# SmartThermo1.net
KiCad netlist of a schematic drawn in EAGLE
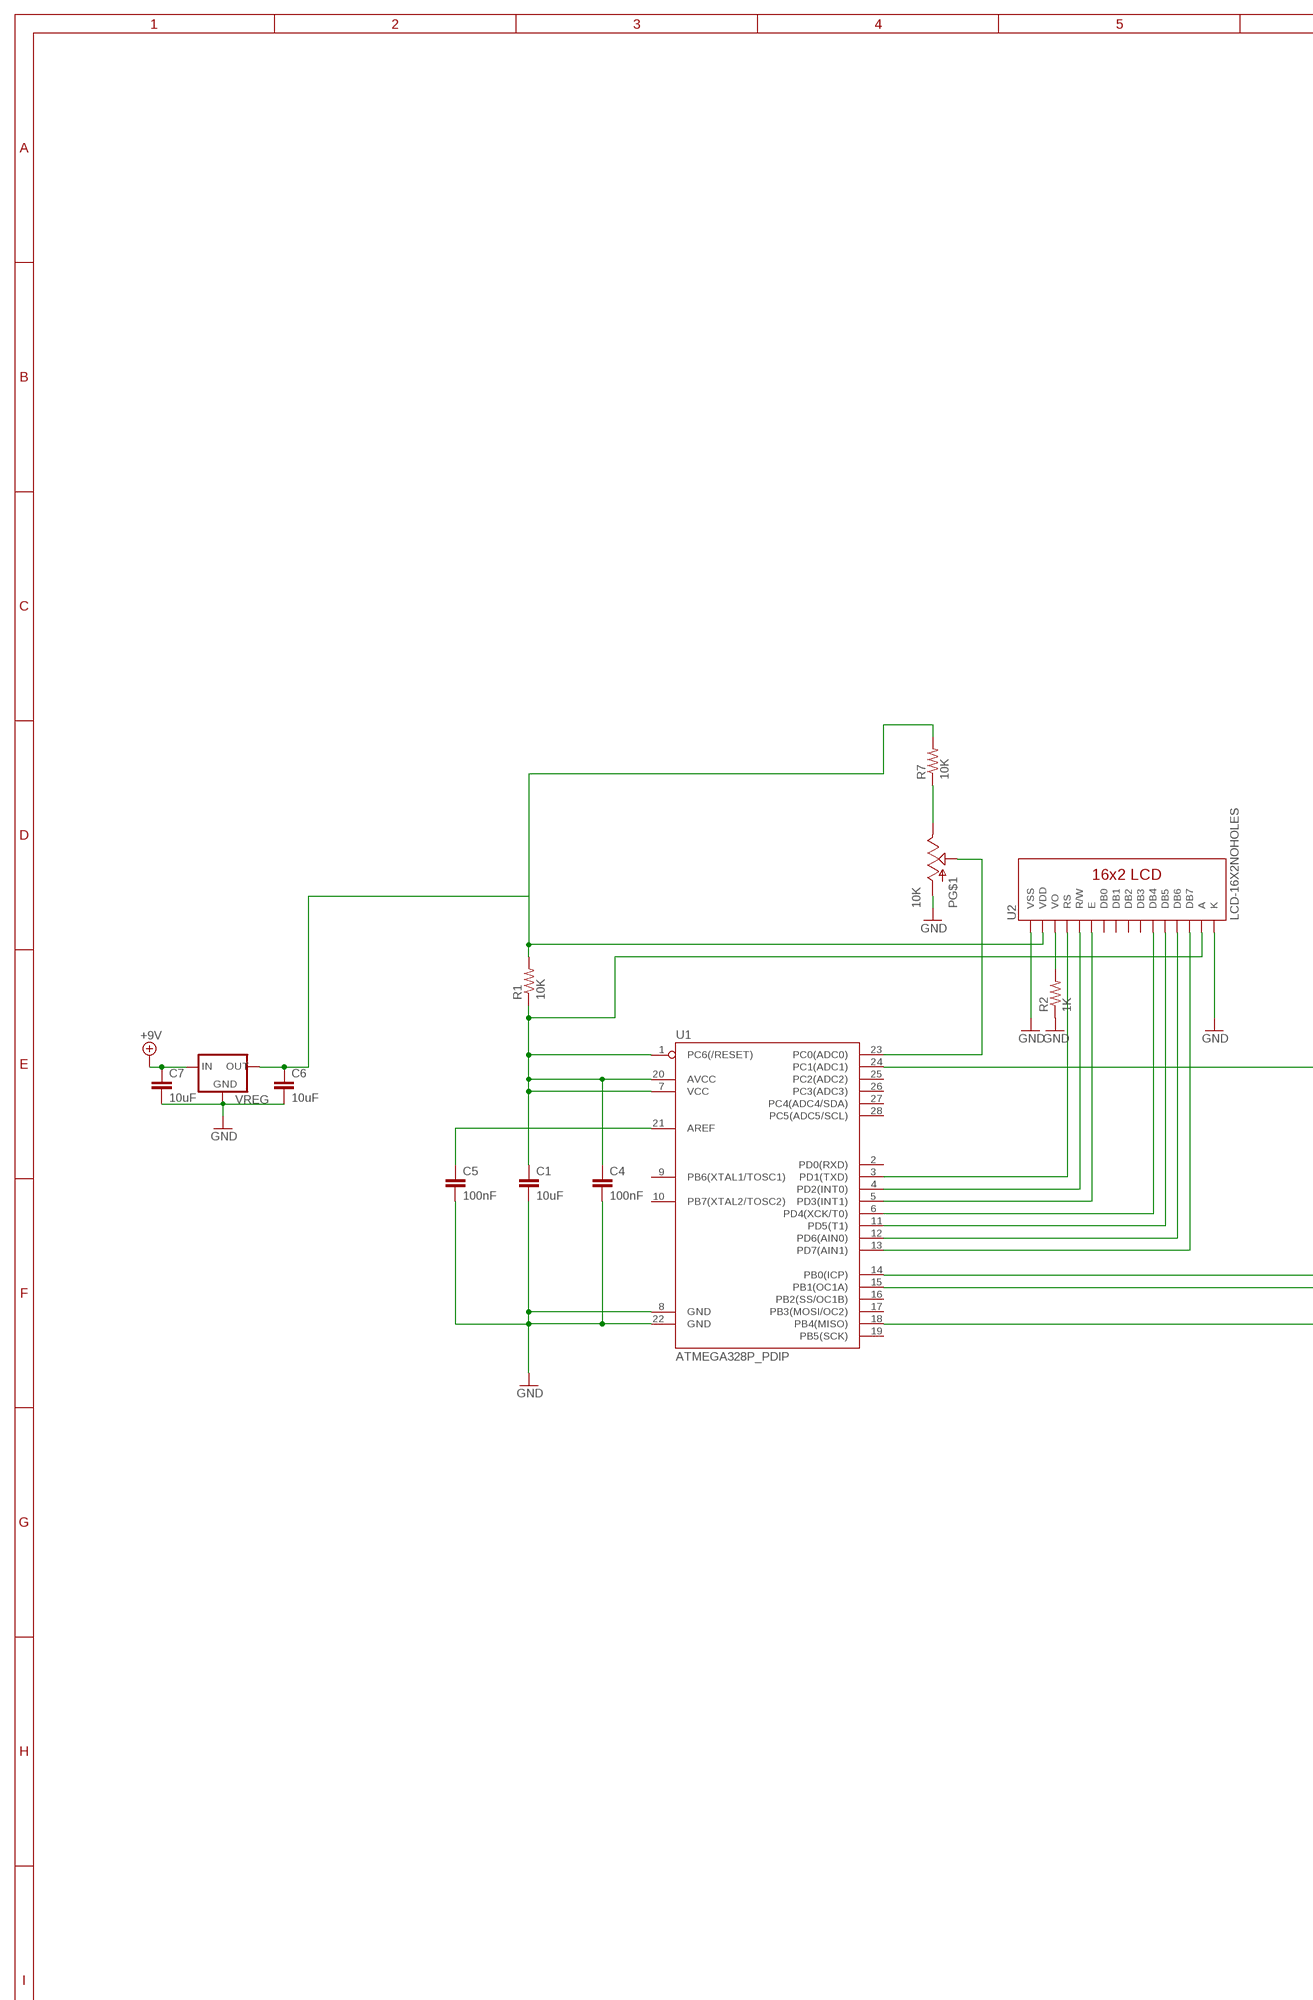
[diagram p0: schematic, sheet 1, part 1 of 2]
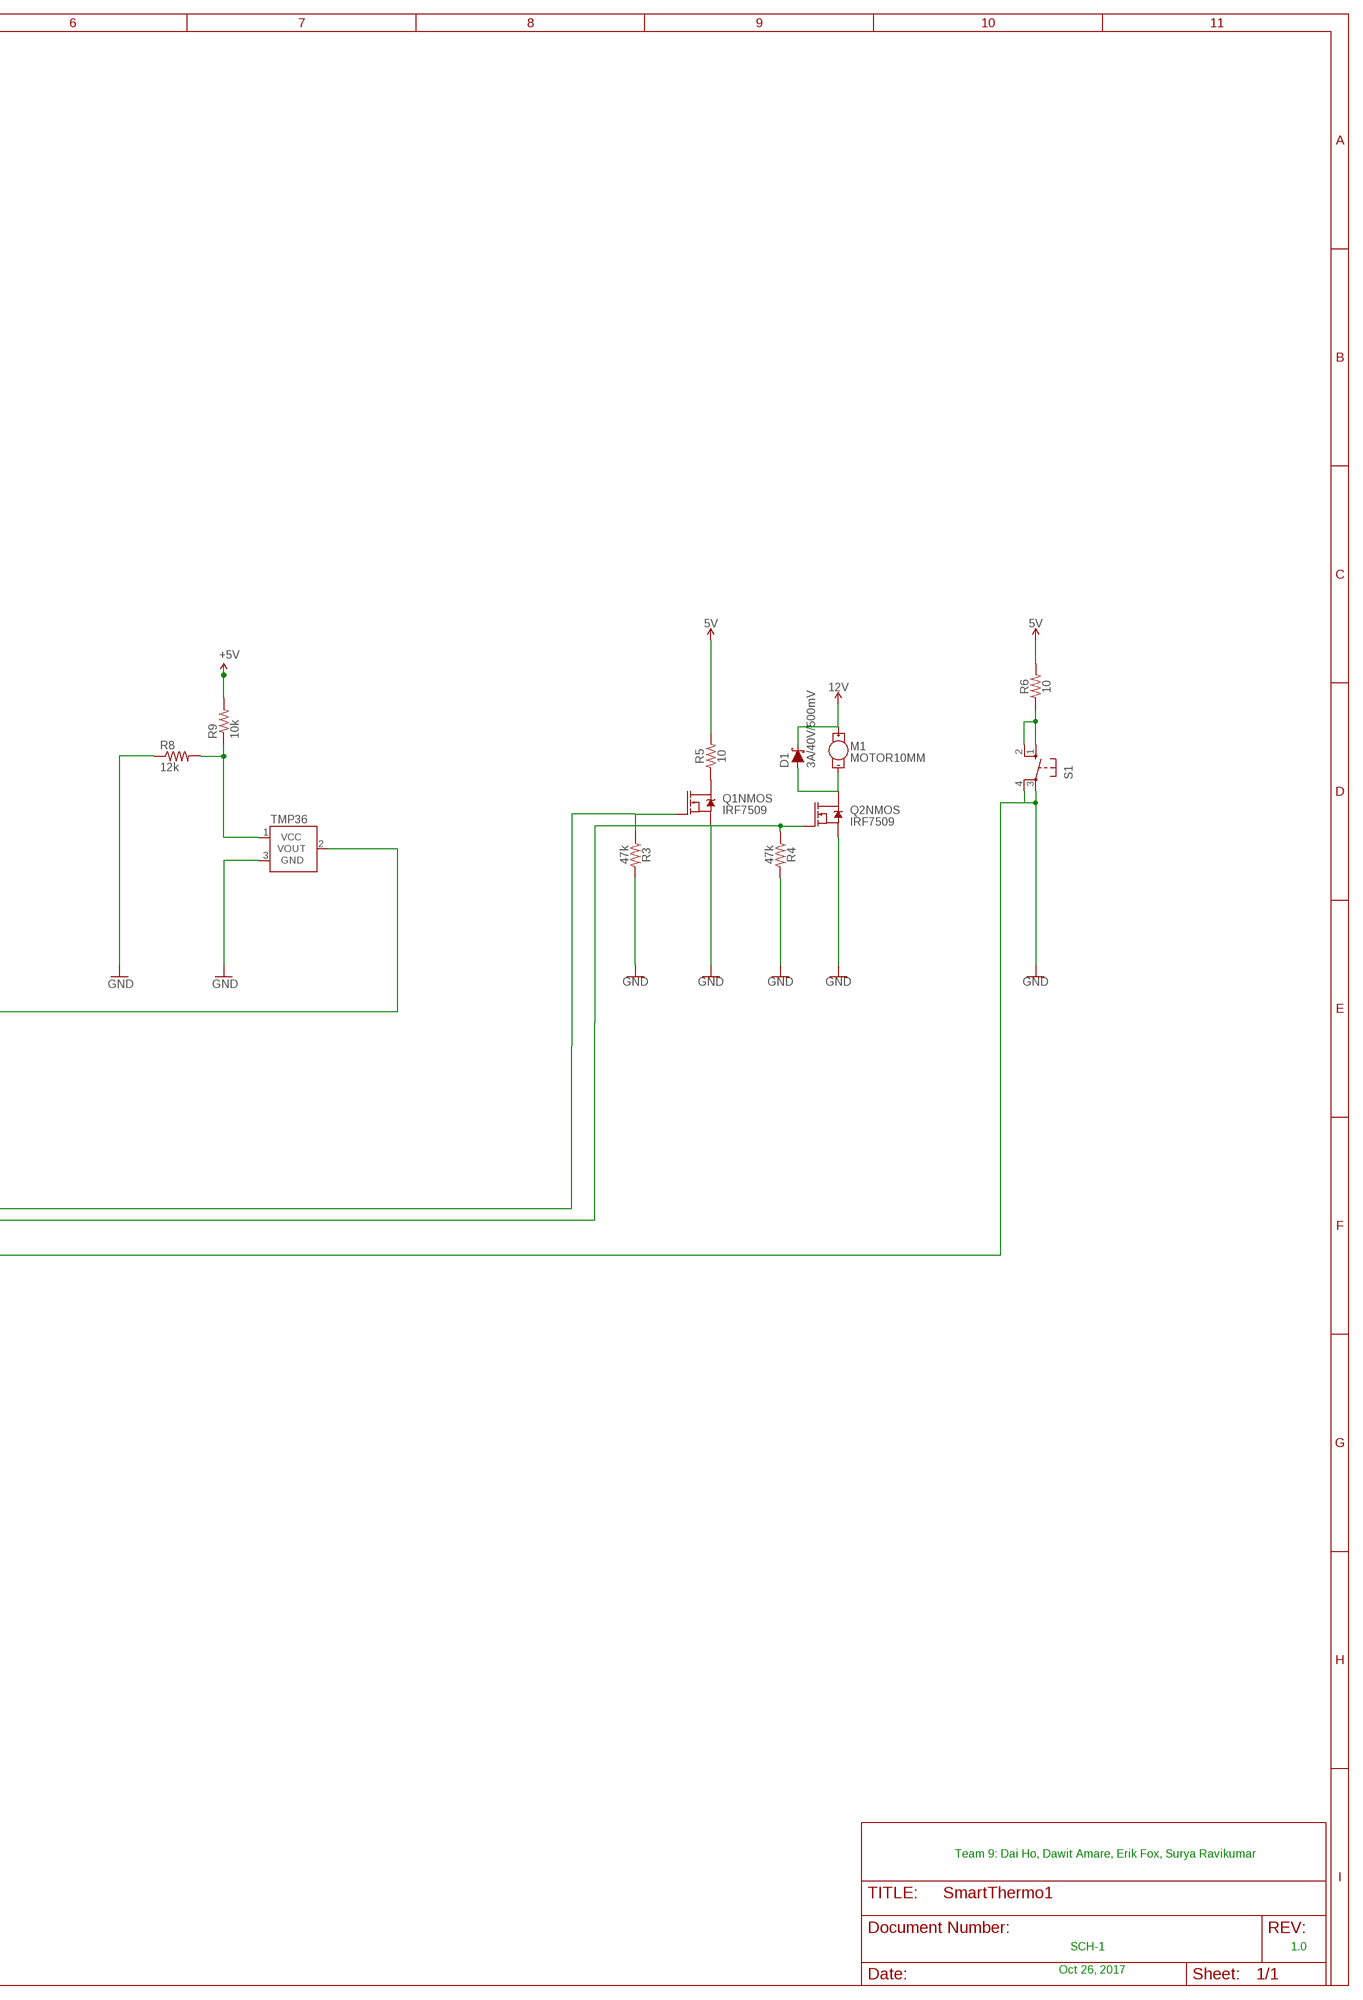
[diagram p1: schematic, sheet 1, part 2 of 2]

(export (version "E")
  (design (tool "Eeschema 10.0.6"))
  (components
    (comp (ref "C1")
      (value "10uF")
      (footprint "eagle-import:1206")
      (libsource (lib "eagle-import") (part "10UF-6.3V-20%(1206)"))
    )
    (comp (ref "C4")
      (value "100nF")
      (footprint "eagle-import:C2.5-2")
      (libsource (lib "eagle-import") (part "C2.5/2"))
    )
    (comp (ref "C5")
      (value "100nF")
      (footprint "eagle-import:C2.5-2")
      (libsource (lib "eagle-import") (part "C2.5/2"))
    )
    (comp (ref "C6")
      (value "10uF")
      (footprint "eagle-import:1206")
      (libsource (lib "eagle-import") (part "10UF-1206-6.3V-20%"))
    )
    (comp (ref "C7")
      (value "10uF")
      (footprint "eagle-import:1206")
      (libsource (lib "eagle-import") (part "10UF-1206-6.3V-20%"))
    )
    (comp (ref "D1")
      (value "3A/40V/500mV")
      (footprint "eagle-import:SMA-DIODE")
      (libsource (lib "eagle-import") (part "DIODE-SCHOTTKY-B340A"))
    )
    (comp (ref "M1")
      (value "MOTOR10MM")
      (footprint "eagle-import:VIBE-MOTOR-10MM")
      (libsource (lib "eagle-import") (part "MOTOR10MM"))
    )
    (comp (ref "P")
      (value "10K")
      (footprint "eagle-import:POT_PTH")
      (libsource (lib "eagle-import") (part "POT_SWITCHPOT_PTH"))
    )
    (comp (ref "Q1")
      (value "IRF7509")
      (footprint "eagle-import:MSOP8")
      (libsource (lib "eagle-import") (part "IRF7509"))
    )
    (comp (ref "Q2")
      (value "IRF7509")
      (footprint "eagle-import:MSOP8")
      (libsource (lib "eagle-import") (part "IRF7509"))
    )
    (comp (ref "R1")
      (value "10K")
      (footprint "eagle-import:1206")
      (libsource (lib "eagle-import") (part "RESISTOR1206"))
    )
    (comp (ref "R2")
      (value "1K")
      (footprint "eagle-import:0603-RES")
      (libsource (lib "eagle-import") (part "1KOHM1/10W1%(0603)"))
    )
    (comp (ref "R3")
      (value "47k")
      (footprint "eagle-import:0603")
      (libsource (lib "eagle-import") (part "47KOHM-0603-1/10W-1%"))
    )
    (comp (ref "R4")
      (value "47k")
      (footprint "eagle-import:0603")
      (libsource (lib "eagle-import") (part "47KOHM-0603-1/10W-1%"))
    )
    (comp (ref "R5")
      (value "10")
      (footprint "eagle-import:0603")
      (libsource (lib "eagle-import") (part "10OHM-0603-1/10W-5%"))
    )
    (comp (ref "R6")
      (value "10")
      (footprint "eagle-import:0603")
      (libsource (lib "eagle-import") (part "10OHM-0603-1/10W-5%"))
    )
    (comp (ref "R7")
      (value "10K")
      (footprint "eagle-import:1206")
      (libsource (lib "eagle-import") (part "RESISTOR1206"))
    )
    (comp (ref "R8")
      (value "12k")
      (footprint "eagle-import:0207_5V")
      (libsource (lib "eagle-import") (part "R-US_0207/5V"))
    )
    (comp (ref "R9")
      (value "10k")
      (footprint "eagle-import:0207_5V")
      (libsource (lib "eagle-import") (part "R-US_0207/5V"))
    )
    (comp (ref "S1")
      (value "10-XX")
      (footprint "eagle-import:B3F-10XX")
      (fields (field (name "MPN") "B3F-1000"))
      (libsource (lib "eagle-import") (part "10-XX"))
    )
    (comp (ref "TMP36")
      (value "TMP36GT9")
      (footprint "eagle-import:TO-92")
      (libsource (lib "eagle-import") (part "TMP36GT9"))
    )
    (comp (ref "U1")
      (value "ATMEGA328P_PDIP")
      (footprint "eagle-import:DIL28-3")
      (libsource (lib "eagle-import") (part "ATMEGA328P_PDIP"))
    )
    (comp (ref "U2")
      (value "LCD-16X2NOHOLES")
      (footprint "eagle-import:LCD-16X2_NOHOLES")
      (libsource (lib "eagle-import") (part "LCD-16X2NOHOLES"))
    )
    (comp (ref "VREG")
      (value "V_REG_78XX-TO-220")
      (footprint "eagle-import:TO-220-ALT")
      (libsource (lib "eagle-import") (part "V_REG_78XX-TO-220"))
    )
  )
  (nets
    (net (code "1") (name "+5V") (class "Default")
      (node (ref "R9") (pin "2") (pinfunction "2_2") (pintype "passive"))
    )
    (net (code "2") (name "+9V") (class "Default")
      (node (ref "C7") (pin "1") (pinfunction "1_1") (pintype "passive"))
      (node (ref "VREG") (pin "IN") (pinfunction "IN_IN") (pintype "input"))
    )
    (net (code "3") (name "5V") (class "Default")
      (node (ref "R5") (pin "2") (pinfunction "2_2") (pintype "passive"))
      (node (ref "R6") (pin "2") (pinfunction "2_2") (pintype "passive"))
    )
    (net (code "4") (name "12V") (class "Default")
      (node (ref "D1") (pin "C") (pinfunction "C_C") (pintype "passive"))
      (node (ref "M1") (pin "+") (pinfunction "+_+") (pintype "bidirectional"))
    )
    (net (code "5") (name "GND") (class "Default")
      (node (ref "C1") (pin "2") (pinfunction "2_2") (pintype "passive"))
      (node (ref "C4") (pin "2") (pinfunction "2_2") (pintype "passive"))
      (node (ref "C5") (pin "2") (pinfunction "2_2") (pintype "passive"))
      (node (ref "C6") (pin "2") (pinfunction "2_2") (pintype "passive"))
      (node (ref "C7") (pin "2") (pinfunction "2_2") (pintype "passive"))
      (node (ref "P") (pin "E@1") (pinfunction "A_E@1") (pintype "passive"))
      (node (ref "Q1") (pin "1") (pinfunction "S_1") (pintype "bidirectional"))
      (node (ref "Q2") (pin "1") (pinfunction "S_1") (pintype "bidirectional"))
      (node (ref "R2") (pin "1") (pinfunction "1_1") (pintype "passive"))
      (node (ref "R3") (pin "2") (pinfunction "2_2") (pintype "passive"))
      (node (ref "R4") (pin "2") (pinfunction "2_2") (pintype "passive"))
      (node (ref "R8") (pin "1") (pinfunction "1_1") (pintype "passive"))
      (node (ref "S1") (pin "3") (pinfunction "P_3") (pintype "passive"))
      (node (ref "S1") (pin "4") (pinfunction "P1_4") (pintype "passive"))
      (node (ref "TMP36") (pin "3") (pinfunction "GND_3") (pintype "bidirectional"))
      (node (ref "U1") (pin "18") (pinfunction "PB4(MISO)_18") (pintype "bidirectional"))
      (node (ref "U1") (pin "22") (pinfunction "GND_22") (pintype "bidirectional"))
      (node (ref "U1") (pin "8") (pinfunction "GND_8") (pintype "bidirectional"))
      (node (ref "U2") (pin "1") (pinfunction "VSS_1") (pintype "power_in"))
      (node (ref "U2") (pin "16") (pinfunction "K_16") (pintype "power_in"))
      (node (ref "VREG") (pin "GND") (pinfunction "GND_GND") (pintype "input"))
    )
    (net (code "6") (name "Net-(D1-PadA)") (class "Default")
      (node (ref "D1") (pin "A") (pinfunction "A_A") (pintype "passive"))
      (node (ref "M1") (pin "-") (pinfunction "-_-") (pintype "bidirectional"))
      (node (ref "Q2") (pin "7") (pinfunction "D_7") (pintype "bidirectional"))
      (node (ref "Q2") (pin "8") (pinfunction "D_8") (pintype "bidirectional"))
    )
    (net (code "7") (name "Net-(PA-E)") (class "Default")
      (node (ref "P") (pin "E@2") (pinfunction "E_E@2") (pintype "passive"))
      (node (ref "R7") (pin "1") (pinfunction "1_1") (pintype "passive"))
    )
    (net (code "8") (name "Net-(PA-S)") (class "Default")
      (node (ref "P") (pin "WAND") (pinfunction "S_WAND") (pintype "passive"))
      (node (ref "U1") (pin "23") (pinfunction "PC0(ADC0)_23") (pintype "bidirectional"))
    )
    (net (code "9") (name "Net-(Q1A-D-Pad7)") (class "Default")
      (node (ref "Q1") (pin "7") (pinfunction "D_7") (pintype "bidirectional"))
      (node (ref "Q1") (pin "8") (pinfunction "D_8") (pintype "bidirectional"))
      (node (ref "R5") (pin "1") (pinfunction "1_1") (pintype "passive"))
    )
    (net (code "10") (name "Net-(Q1A-G)") (class "Default")
      (node (ref "Q1") (pin "2") (pinfunction "G_2") (pintype "bidirectional"))
      (node (ref "R3") (pin "1") (pinfunction "1_1") (pintype "passive"))
      (node (ref "U1") (pin "14") (pinfunction "PB0(ICP)_14") (pintype "bidirectional"))
    )
    (net (code "11") (name "Net-(Q2A-G)") (class "Default")
      (node (ref "Q2") (pin "2") (pinfunction "G_2") (pintype "bidirectional"))
      (node (ref "R4") (pin "1") (pinfunction "1_1") (pintype "passive"))
      (node (ref "U1") (pin "15") (pinfunction "PB1(OC1A)_15") (pintype "bidirectional"))
    )
    (net (code "12") (name "Net-(S1-S)") (class "Default")
      (node (ref "R6") (pin "1") (pinfunction "1_1") (pintype "passive"))
      (node (ref "S1") (pin "1") (pinfunction "S_1") (pintype "passive"))
      (node (ref "S1") (pin "2") (pinfunction "S1_2") (pintype "passive"))
    )
    (net (code "13") (name "Net-(TMP36-VCC)") (class "Default")
      (node (ref "R8") (pin "2") (pinfunction "2_2") (pintype "passive"))
      (node (ref "R9") (pin "1") (pinfunction "1_1") (pintype "passive"))
      (node (ref "TMP36") (pin "1") (pinfunction "VCC_1") (pintype "bidirectional"))
    )
    (net (code "14") (name "Net-(TMP36-VOUT)") (class "Default")
      (node (ref "TMP36") (pin "2") (pinfunction "VOUT_2") (pintype "bidirectional"))
      (node (ref "U1") (pin "24") (pinfunction "PC1(ADC1)_24") (pintype "bidirectional"))
    )
    (net (code "15") (name "Net-(U1-AREF)") (class "Default")
      (node (ref "C5") (pin "1") (pinfunction "1_1") (pintype "passive"))
      (node (ref "U1") (pin "21") (pinfunction "AREF_21") (pintype "bidirectional"))
    )
    (net (code "16") (name "Net-(U1-AVCC)") (class "Default")
      (node (ref "C1") (pin "1") (pinfunction "1_1") (pintype "passive"))
      (node (ref "C4") (pin "1") (pinfunction "1_1") (pintype "passive"))
      (node (ref "R1") (pin "1") (pinfunction "1_1") (pintype "passive"))
      (node (ref "U1") (pin "1") (pinfunction "PC6(/RESET)_1") (pintype "bidirectional"))
      (node (ref "U1") (pin "20") (pinfunction "AVCC_20") (pintype "bidirectional"))
      (node (ref "U1") (pin "7") (pinfunction "VCC_7") (pintype "bidirectional"))
      (node (ref "U2") (pin "15") (pinfunction "A_15") (pintype "power_in"))
    )
    (net (code "17") (name "Net-(U1-PD1(TXD))") (class "Default")
      (node (ref "U1") (pin "3") (pinfunction "PD1(TXD)_3") (pintype "bidirectional"))
      (node (ref "U2") (pin "4") (pinfunction "RS_4") (pintype "input"))
    )
    (net (code "18") (name "Net-(U1-PD2(INT0))") (class "Default")
      (node (ref "U1") (pin "4") (pinfunction "PD2(INT0)_4") (pintype "bidirectional"))
      (node (ref "U2") (pin "5") (pinfunction "R/W_5") (pintype "input"))
    )
    (net (code "19") (name "Net-(U1-PD3(INT1))") (class "Default")
      (node (ref "U1") (pin "5") (pinfunction "PD3(INT1)_5") (pintype "bidirectional"))
      (node (ref "U2") (pin "6") (pinfunction "E_6") (pintype "input"))
    )
    (net (code "20") (name "Net-(U1-PD4(XCK{slash}T0))") (class "Default")
      (node (ref "U1") (pin "6") (pinfunction "PD4(XCK/T0)_6") (pintype "bidirectional"))
      (node (ref "U2") (pin "11") (pinfunction "DB4_11") (pintype "bidirectional"))
    )
    (net (code "21") (name "Net-(U1-PD5(T1))") (class "Default")
      (node (ref "U1") (pin "11") (pinfunction "PD5(T1)_11") (pintype "bidirectional"))
      (node (ref "U2") (pin "12") (pinfunction "DB5_12") (pintype "bidirectional"))
    )
    (net (code "22") (name "Net-(U1-PD6(AIN0))") (class "Default")
      (node (ref "U1") (pin "12") (pinfunction "PD6(AIN0)_12") (pintype "bidirectional"))
      (node (ref "U2") (pin "13") (pinfunction "DB6_13") (pintype "bidirectional"))
    )
    (net (code "23") (name "Net-(U1-PD7(AIN1))") (class "Default")
      (node (ref "U1") (pin "13") (pinfunction "PD7(AIN1)_13") (pintype "bidirectional"))
      (node (ref "U2") (pin "14") (pinfunction "DB7_14") (pintype "bidirectional"))
    )
    (net (code "24") (name "Net-(U2-VDD)") (class "Default")
      (node (ref "C6") (pin "1") (pinfunction "1_1") (pintype "passive"))
      (node (ref "R1") (pin "2") (pinfunction "2_2") (pintype "passive"))
      (node (ref "R7") (pin "2") (pinfunction "2_2") (pintype "passive"))
      (node (ref "U2") (pin "2") (pinfunction "VDD_2") (pintype "power_in"))
      (node (ref "VREG") (pin "OUT") (pinfunction "OUT_OUT") (pintype "output"))
    )
    (net (code "25") (name "Net-(U2-VO)") (class "Default")
      (node (ref "R2") (pin "2") (pinfunction "2_2") (pintype "passive"))
      (node (ref "U2") (pin "3") (pinfunction "VO_3") (pintype "bidirectional"))
    )
    (net (code "26") (name "unconnected-(U1-PB2(SS{slash}OC1B)-Pad16)") (class "Default")
      (node (ref "U1") (pin "16") (pinfunction "PB2(SS/OC1B)_16") (pintype "bidirectional"))
    )
    (net (code "27") (name "unconnected-(U1-PB3(MOSI{slash}OC2)-Pad17)") (class "Default")
      (node (ref "U1") (pin "17") (pinfunction "PB3(MOSI/OC2)_17") (pintype "bidirectional"))
    )
    (net (code "28") (name "unconnected-(U1-PB5(SCK)-Pad19)") (class "Default")
      (node (ref "U1") (pin "19") (pinfunction "PB5(SCK)_19") (pintype "bidirectional"))
    )
    (net (code "29") (name "unconnected-(U1-PB6(XTAL1{slash}TOSC1)-Pad9)") (class "Default")
      (node (ref "U1") (pin "9") (pinfunction "PB6(XTAL1/TOSC1)_9") (pintype "bidirectional"))
    )
    (net (code "30") (name "unconnected-(U1-PB7(XTAL2{slash}TOSC2)-Pad10)") (class "Default")
      (node (ref "U1") (pin "10") (pinfunction "PB7(XTAL2/TOSC2)_10") (pintype "bidirectional"))
    )
    (net (code "31") (name "unconnected-(U1-PC2(ADC2)-Pad25)") (class "Default")
      (node (ref "U1") (pin "25") (pinfunction "PC2(ADC2)_25") (pintype "bidirectional"))
    )
    (net (code "32") (name "unconnected-(U1-PC3(ADC3)-Pad26)") (class "Default")
      (node (ref "U1") (pin "26") (pinfunction "PC3(ADC3)_26") (pintype "bidirectional"))
    )
    (net (code "33") (name "unconnected-(U1-PC4(ADC4{slash}SDA)-Pad27)") (class "Default")
      (node (ref "U1") (pin "27") (pinfunction "PC4(ADC4/SDA)_27") (pintype "bidirectional"))
    )
    (net (code "34") (name "unconnected-(U1-PC5(ADC5{slash}SCL)-Pad28)") (class "Default")
      (node (ref "U1") (pin "28") (pinfunction "PC5(ADC5/SCL)_28") (pintype "bidirectional"))
    )
    (net (code "35") (name "unconnected-(U1-PD0(RXD)-Pad2)") (class "Default")
      (node (ref "U1") (pin "2") (pinfunction "PD0(RXD)_2") (pintype "bidirectional"))
    )
    (net (code "36") (name "unconnected-(U2-DB0-Pad7)") (class "Default")
      (node (ref "U2") (pin "7") (pinfunction "DB0_7") (pintype "bidirectional"))
    )
    (net (code "37") (name "unconnected-(U2-DB1-Pad8)") (class "Default")
      (node (ref "U2") (pin "8") (pinfunction "DB1_8") (pintype "bidirectional"))
    )
    (net (code "38") (name "unconnected-(U2-DB2-Pad9)") (class "Default")
      (node (ref "U2") (pin "9") (pinfunction "DB2_9") (pintype "bidirectional"))
    )
    (net (code "39") (name "unconnected-(U2-DB3-Pad10)") (class "Default")
      (node (ref "U2") (pin "10") (pinfunction "DB3_10") (pintype "bidirectional"))
    )
  )
)
